# DA_10_-10.net
KiCad netlist of a schematic drawn in Altium Designer
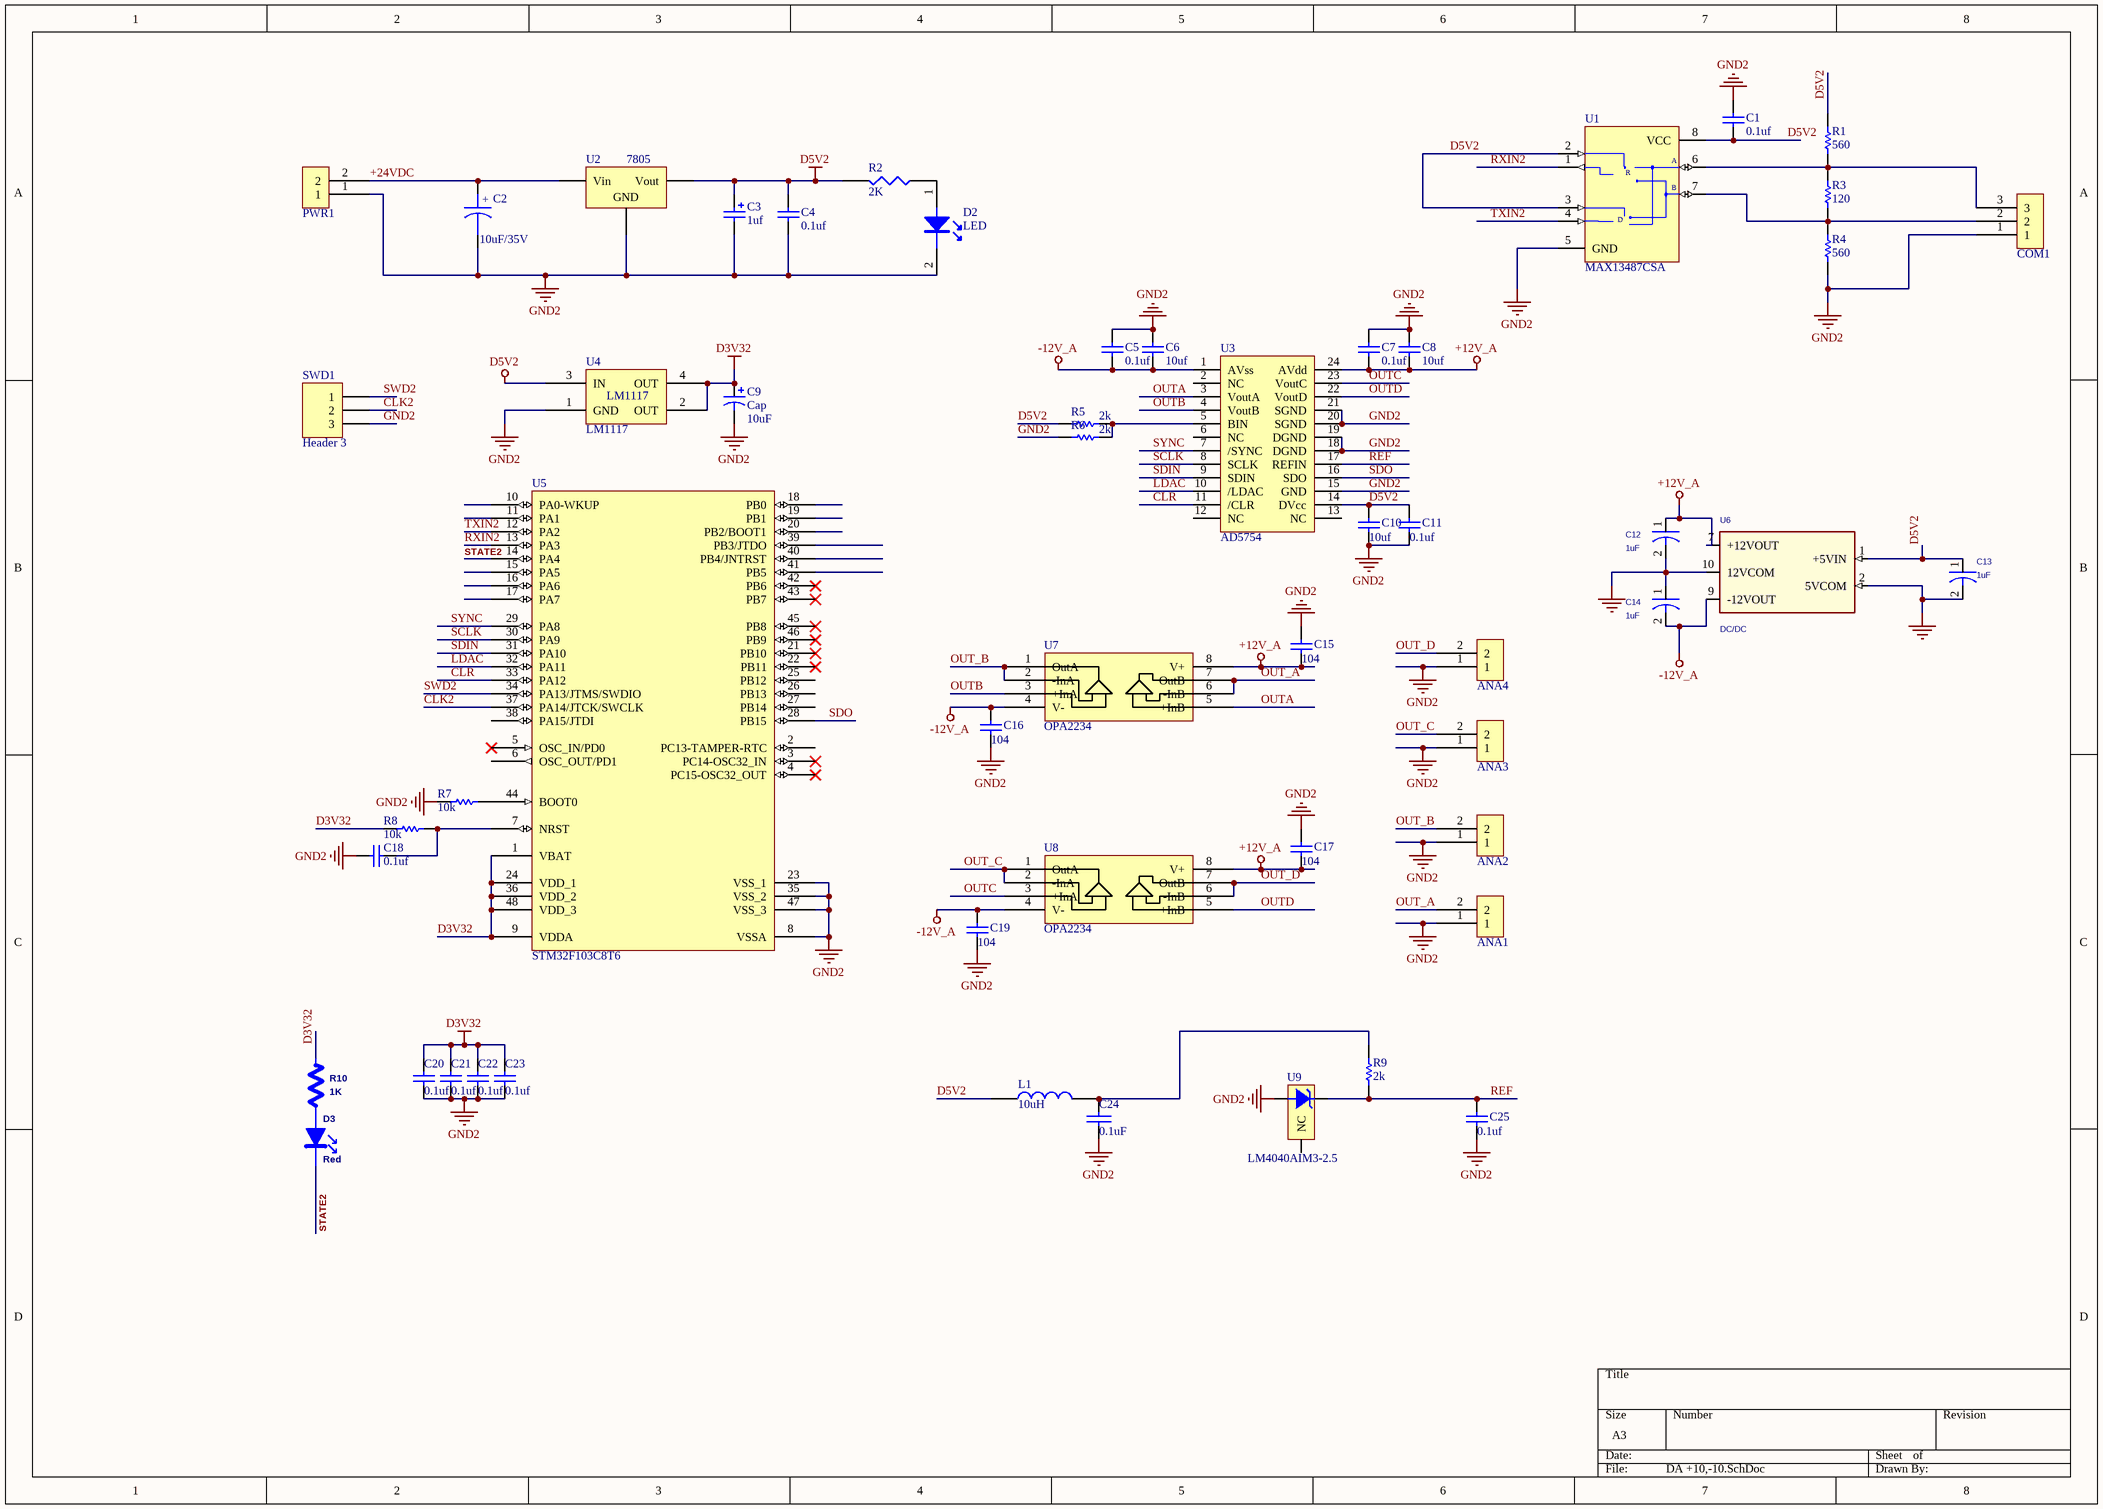
[diagram p0: DA +10,-10.SchDoc]

(export (version "E")
  (design (tool "Eeschema 10.0.6"))
  (components
    (comp (ref "ANA1")
      (value "HDR1*2_3.81")
      (footprint "2P HEADER 3.81 90")
      (libsource (lib "我的器件库") (part "HDR1*2_3.81"))
    )
    (comp (ref "ANA2")
      (value "HDR1*2_3.81")
      (footprint "2P HEADER 3.81 90")
      (libsource (lib "我的器件库") (part "HDR1*2_3.81"))
    )
    (comp (ref "ANA3")
      (value "HDR1*2_3.81")
      (footprint "2P HEADER 3.81 90")
      (libsource (lib "我的器件库") (part "HDR1*2_3.81"))
    )
    (comp (ref "ANA4")
      (value "HDR1*2_3.81")
      (footprint "2P HEADER 3.81 90")
      (libsource (lib "我的器件库") (part "HDR1*2_3.81"))
    )
    (comp (ref "C1")
      (value "0.1uf")
      (footprint "EIA-0805")
      (description "Capacitor")
      (fields (field (name "PUBLISHER") "Altium Limited"))
      (libsource (lib "Miscellaneous Devices") (part "Cap"))
    )
    (comp (ref "C2")
      (value "10uF/35V")
      (footprint "BC-CAP 6.6 X5.4")
      (description "Capacitor")
      (libsource (lib "*") (part "CAPACITOR POL"))
    )
    (comp (ref "C3") (value "1uf") (footprint "EIA-0805") (libsource (lib "我的器件库") (part "CAP")))
    (comp (ref "C4") (value "0.1uf") (footprint "EIA-0805") (libsource (lib "我的器件库") (part "CAP Y1")))
    (comp (ref "C5")
      (value "0.1uf")
      (footprint "EIA-0805")
      (description "Capacitor")
      (fields (field (name "Comment") "1uf") (field (name "PUBLISHER") "Altium Limited"))
      (libsource (lib "Miscellaneous Devices") (part "Cap"))
    )
    (comp (ref "C6")
      (value "10uf")
      (footprint "EIA-0805")
      (description "Capacitor")
      (fields (field (name "Comment") "1uf") (field (name "PUBLISHER") "Altium Limited"))
      (libsource (lib "Miscellaneous Devices") (part "Cap"))
    )
    (comp (ref "C7")
      (value "0.1uf")
      (footprint "EIA-0805")
      (description "Capacitor")
      (fields (field (name "Comment") "1uf") (field (name "PUBLISHER") "Altium Limited"))
      (libsource (lib "Miscellaneous Devices") (part "Cap"))
    )
    (comp (ref "C8")
      (value "10uf")
      (footprint "EIA-0805")
      (description "Capacitor")
      (fields (field (name "Comment") "1uf") (field (name "PUBLISHER") "Altium Limited"))
      (libsource (lib "Miscellaneous Devices") (part "Cap"))
    )
    (comp (ref "C9")
      (value "Cap")
      (footprint "EIA-0805")
      (description "Polarized Capacitor (Radial)")
      (fields (field (name "ALTIUM_VALUE") "10uF") (field (name "PUBLISHER") "Altium Limited"))
      (libsource (lib "Miscellaneous Devices") (part "Cap Pol1"))
    )
    (comp (ref "C10")
      (value "10uf")
      (footprint "EIA-0805")
      (description "Capacitor")
      (fields (field (name "Comment") "1uf") (field (name "PUBLISHER") "Altium Limited"))
      (libsource (lib "Miscellaneous Devices") (part "Cap"))
    )
    (comp (ref "C11")
      (value "0.1uf")
      (footprint "EIA-0805")
      (description "Capacitor")
      (fields (field (name "Comment") "1uf") (field (name "PUBLISHER") "Altium Limited"))
      (libsource (lib "Miscellaneous Devices") (part "Cap"))
    )
    (comp (ref "C12")
      (value "1uF")
      (fields
        (field (name "MFGRS PART NUM") "ECJ-3YB1E105K")
        (field (name "PART NUMBER") "CAP-500525")
        (field (name "MANUFACTURER") "Panasonic")
      )
      (libsource (lib "*") (part "CAP"))
    )
    (comp (ref "C13")
      (value "1uF")
      (fields
        (field (name "MFGRS PART NUM") "ECJ-3YB1E105K")
        (field (name "PART NUMBER") "CAP-500525")
        (field (name "MANUFACTURER") "Panasonic")
      )
      (libsource (lib "*") (part "CAP"))
    )
    (comp (ref "C14")
      (value "1uF")
      (fields
        (field (name "MFGRS PART NUM") "ECJ-3YB1E105K")
        (field (name "PART NUMBER") "CAP-500525")
        (field (name "MANUFACTURER") "Panasonic")
      )
      (libsource (lib "*") (part "CAP"))
    )
    (comp (ref "C15")
      (value "104")
      (footprint "EIA-0805")
      (description "Capacitor")
      (fields (field (name "Comment") "1uf") (field (name "PUBLISHER") "Altium Limited"))
      (libsource (lib "Miscellaneous Devices") (part "Cap"))
    )
    (comp (ref "C16")
      (value "104")
      (footprint "EIA-0805")
      (description "Capacitor")
      (fields (field (name "Comment") "1uf") (field (name "PUBLISHER") "Altium Limited"))
      (libsource (lib "Miscellaneous Devices") (part "Cap"))
    )
    (comp (ref "C17")
      (value "104")
      (footprint "EIA-0805")
      (description "Capacitor")
      (fields (field (name "Comment") "1uf") (field (name "PUBLISHER") "Altium Limited"))
      (libsource (lib "Miscellaneous Devices") (part "Cap"))
    )
    (comp (ref "C18")
      (value "0.1uf")
      (footprint "EIA-0805")
      (description "Capacitor")
      (fields (field (name "PUBLISHER") "Altium Limited"))
      (libsource (lib "Miscellaneous Devices") (part "Cap"))
    )
    (comp (ref "C19")
      (value "104")
      (footprint "EIA-0805")
      (description "Capacitor")
      (fields (field (name "Comment") "1uf") (field (name "PUBLISHER") "Altium Limited"))
      (libsource (lib "Miscellaneous Devices") (part "Cap"))
    )
    (comp (ref "C20")
      (value "0.1uf")
      (footprint "EIA-0805")
      (description "Capacitor")
      (fields (field (name "PUBLISHER") "Altium Limited"))
      (libsource (lib "Miscellaneous Devices") (part "Cap"))
    )
    (comp (ref "C21")
      (value "0.1uf")
      (footprint "EIA-0805")
      (description "Capacitor")
      (fields (field (name "PUBLISHER") "Altium Limited"))
      (libsource (lib "Miscellaneous Devices") (part "Cap"))
    )
    (comp (ref "C22")
      (value "0.1uf")
      (footprint "EIA-0805")
      (description "Capacitor")
      (fields (field (name "PUBLISHER") "Altium Limited"))
      (libsource (lib "Miscellaneous Devices") (part "Cap"))
    )
    (comp (ref "C23")
      (value "0.1uf")
      (footprint "EIA-0805")
      (description "Capacitor")
      (fields (field (name "PUBLISHER") "Altium Limited"))
      (libsource (lib "Miscellaneous Devices") (part "Cap"))
    )
    (comp (ref "C24")
      (value "0.1uF")
      (footprint "EIA-0805")
      (description "Capacitor")
      (libsource (lib "") (part "CAP_1"))
    )
    (comp (ref "C25")
      (value "0.1uf")
      (footprint "EIA-0805")
      (description "Capacitor")
      (fields (field (name "Comment") "1uf") (field (name "PUBLISHER") "Altium Limited"))
      (libsource (lib "Miscellaneous Devices") (part "Cap"))
    )
    (comp (ref "COM1")
      (value "HDR1*3_3.81")
      (footprint "3P HEADER 3.81 90")
      (libsource (lib "我的器件库") (part "HDR1*3_3.81"))
    )
    (comp (ref "D2") (value "LED") (footprint "0805_L") (libsource (lib "backup of send") (part "LED")))
    (comp (ref "D3")
      (value "BC_LED")
      (footprint "0805_L")
      (fields (field (name "COLOR") "Red"))
      (libsource (lib "TYT") (part "BC_LED"))
    )
    (comp (ref "L1") (value "10uH") (footprint "C1206") (libsource (lib "*") (part "INDUCTOR")))
    (comp (ref "PWR1")
      (value "HDR1*2_3.81")
      (footprint "2P HEADER 3.81 90")
      (libsource (lib "") (part "HDR1*2_3.81_1"))
    )
    (comp (ref "R1")
      (value "560")
      (footprint "EIA-0805")
      (description "Resistor")
      (fields (field (name "PUBLISHER") "Altium Limited"))
      (libsource (lib "Miscellaneous Devices") (part "Res1"))
    )
    (comp (ref "R2") (value "2K") (footprint "EIA-0805") (libsource (lib "*") (part "RES1")))
    (comp (ref "R3")
      (value "120")
      (footprint "EIA-0805")
      (description "Resistor")
      (fields (field (name "PUBLISHER") "Altium Limited"))
      (libsource (lib "Miscellaneous Devices") (part "Res1"))
    )
    (comp (ref "R4")
      (value "560")
      (footprint "EIA-0805")
      (description "Resistor")
      (fields (field (name "PUBLISHER") "Altium Limited"))
      (libsource (lib "Miscellaneous Devices") (part "Res1"))
    )
    (comp (ref "R5")
      (value "2k")
      (footprint "EIA-0805")
      (description "Resistor")
      (fields (field (name "PUBLISHER") "Altium Limited"))
      (libsource (lib "Miscellaneous Devices") (part "Res1"))
    )
    (comp (ref "R6")
      (value "2k")
      (footprint "EIA-0805")
      (description "Resistor")
      (fields (field (name "PUBLISHER") "Altium Limited"))
      (libsource (lib "Miscellaneous Devices") (part "Res1"))
    )
    (comp (ref "R7")
      (value "10k")
      (footprint "EIA-0805")
      (description "Resistor")
      (fields (field (name "PUBLISHER") "Altium Limited"))
      (libsource (lib "Miscellaneous Devices") (part "Res1"))
    )
    (comp (ref "R8")
      (value "10k")
      (footprint "EIA-0805")
      (description "Resistor")
      (fields (field (name "PUBLISHER") "Altium Limited"))
      (libsource (lib "Miscellaneous Devices") (part "Res1"))
    )
    (comp (ref "R9")
      (value "2k")
      (footprint "EIA-0805")
      (description "Resistor")
      (fields (field (name "PUBLISHER") "Altium Limited"))
      (libsource (lib "Miscellaneous Devices") (part "Res1"))
    )
    (comp (ref "R10") (value "1K") (footprint "EIA-0805") (libsource (lib "TYT") (part "BC_R")))
    (comp (ref "SWD1")
      (value "Header 3")
      (footprint "HDR1X3")
      (description "Header, 3-Pin")
      (fields (field (name "PUBLISHER") "Altium Limited"))
      (libsource (lib "Miscellaneous Connectors") (part "Header 3"))
    )
    (comp (ref "U1")
      (value "MAX13487CSA")
      (footprint "SO8_L")
      (description "Low-Power, Slew-Rate-Limited RS-485/RS-422 Transceiver")
      (fields (field (name "PUBLISHER") "Altium Limited"))
      (libsource (lib "Maxim Communication Transceiver") (part "MAX485CSA"))
    )
    (comp (ref "U2")
      (value "7805")
      (footprint "TO220")
      (description "Voltage Regulator")
      (fields (field (name "PUBLISHER") "Altium Limited"))
      (libsource (lib "Miscellaneous Devices") (part "Volt Reg"))
    )
    (comp (ref "U3") (value "AD5754") (footprint "TSSOP_24") (libsource (lib "我的器件库") (part "AD5754")))
    (comp (ref "U4") (value "LM1117") (footprint "SOT223_L") (libsource (lib "TYT") (part "LM1117")))
    (comp (ref "U5")
      (value "STM32F103C8T6")
      (footprint "PQFP-48-7*7")
      (description "STM32 ARM-based 32-bit MCU with 64 Kbytes Flash, 48-pin LQFP, Industrial Temperature")
      (fields (field (name "PUBLISHER") "Altium Limited"))
      (libsource (lib "ST Microcontroller 32-Bit STM32") (part "STM32F103C8T6"))
    )
    (comp (ref "U6")
      (value "DC/DC")
      (fields
        (field (name "MANUFACTURER") "Power One")
        (field (name "PART NUMBER") "ASY-503927")
        (field (name "MFGRS PART NUM") "DSP1N5D12")
      )
      (libsource (lib "*") (part "DC/DC-051212_0"))
    )
    (comp (ref "U7") (value "OPA2234") (footprint "SO8_L") (libsource (lib "我的封装") (part "OPA2234")))
    (comp (ref "U8") (value "OPA2234") (footprint "SO8_L") (libsource (lib "我的封装") (part "OPA2234")))
    (comp (ref "U9")
      (value "LM4040AIM3-2.5")
      (footprint "SOT23_L")
      (description "Precision Micropower Shunt Voltage Reference")
      (fields
        (field (name "MANUFACTURER") "National Semiconductor")
        (field (name "DIGIKEYPARTNUMBER") "LM4040AIM3-2.5CT-ND")
        (field (name "PUBLISHER") "Altium Limited")
      )
      (libsource (lib "NSC Voltage Reference") (part "LM4040AIM3-2.5"))
    )
  )
  (nets
    (net (code "1") (name "+12V_A") (class "Default")
      (node (ref "C12") (pin "1") (pinfunction "1_1") (pintype "passive"))
      (node (ref "C15") (pin "2") (pinfunction "2_2") (pintype "passive"))
      (node (ref "C17") (pin "2") (pinfunction "2_2") (pintype "passive"))
      (node (ref "C7") (pin "1") (pinfunction "1_1") (pintype "passive"))
      (node (ref "C8") (pin "1") (pinfunction "1_1") (pintype "passive"))
      (node (ref "U3") (pin "24") (pinfunction "AVdd_24") (pintype "passive"))
      (node (ref "U6") (pin "7") (pinfunction "+12VOUT_7") (pintype "passive"))
      (node (ref "U7") (pin "8") (pinfunction "V+_8") (pintype "passive"))
      (node (ref "U8") (pin "8") (pinfunction "V+_8") (pintype "passive"))
    )
    (net (code "2") (name "-12V_A") (class "Default")
      (node (ref "C14") (pin "2") (pinfunction "2_2") (pintype "passive"))
      (node (ref "C16") (pin "1") (pinfunction "1_1") (pintype "passive"))
      (node (ref "C19") (pin "1") (pinfunction "1_1") (pintype "passive"))
      (node (ref "C5") (pin "1") (pinfunction "1_1") (pintype "passive"))
      (node (ref "C6") (pin "1") (pinfunction "1_1") (pintype "passive"))
      (node (ref "U3") (pin "1") (pinfunction "AVss_1") (pintype "passive"))
      (node (ref "U6") (pin "9") (pinfunction "-12VOUT_9") (pintype "passive"))
      (node (ref "U7") (pin "4") (pinfunction "V-_4") (pintype "passive"))
      (node (ref "U8") (pin "4") (pinfunction "V-_4") (pintype "passive"))
    )
    (net (code "3") (name "/+24VDC") (class "Default")
      (node (ref "C2") (pin "1") (pinfunction "1_1") (pintype "passive"))
      (node (ref "PWR1") (pin "2") (pinfunction "2_2") (pintype "passive"))
      (node (ref "U2") (pin "1") (pinfunction "Vin_1") (pintype "passive"))
    )
    (net (code "4") (name "/CLK2") (class "Default")
      (node (ref "SWD1") (pin "2") (pinfunction "2_2") (pintype "passive"))
      (node (ref "U5") (pin "37") (pinfunction "PA14/JTCK/SWCLK_37") (pintype "bidirectional"))
    )
    (net (code "5") (name "/CLR") (class "Default")
      (node (ref "U3") (pin "11") (pinfunction "/CLR_11") (pintype "passive"))
      (node (ref "U5") (pin "33") (pinfunction "PA12_33") (pintype "bidirectional"))
    )
    (net (code "6") (name "/LDAC") (class "Default")
      (node (ref "U3") (pin "10") (pinfunction "/LDAC_10") (pintype "passive"))
      (node (ref "U5") (pin "32") (pinfunction "PA11_32") (pintype "bidirectional"))
    )
    (net (code "7") (name "/OUTA") (class "Default")
      (node (ref "U3") (pin "3") (pinfunction "VoutA_3") (pintype "passive"))
      (node (ref "U7") (pin "5") (pinfunction "+InB_5") (pintype "passive"))
    )
    (net (code "8") (name "/OUTB") (class "Default")
      (node (ref "U3") (pin "4") (pinfunction "VoutB_4") (pintype "passive"))
      (node (ref "U7") (pin "3") (pinfunction "+InA_3") (pintype "passive"))
    )
    (net (code "9") (name "/OUTC") (class "Default")
      (node (ref "U3") (pin "23") (pinfunction "VoutC_23") (pintype "passive"))
      (node (ref "U8") (pin "3") (pinfunction "+InA_3") (pintype "passive"))
    )
    (net (code "10") (name "/OUTD") (class "Default")
      (node (ref "U3") (pin "22") (pinfunction "VoutD_22") (pintype "passive"))
      (node (ref "U8") (pin "5") (pinfunction "+InB_5") (pintype "passive"))
    )
    (net (code "11") (name "/OUT_A") (class "Default")
      (node (ref "ANA1") (pin "2") (pinfunction "2_2") (pintype "passive"))
      (node (ref "U7") (pin "6") (pinfunction "-InB_6") (pintype "passive"))
      (node (ref "U7") (pin "7") (pinfunction "OutB_7") (pintype "passive"))
    )
    (net (code "12") (name "/OUT_B") (class "Default")
      (node (ref "ANA2") (pin "2") (pinfunction "2_2") (pintype "passive"))
      (node (ref "U7") (pin "1") (pinfunction "OutA_1") (pintype "passive"))
      (node (ref "U7") (pin "2") (pinfunction "-InA_2") (pintype "passive"))
    )
    (net (code "13") (name "/OUT_C") (class "Default")
      (node (ref "ANA3") (pin "2") (pinfunction "2_2") (pintype "passive"))
      (node (ref "U8") (pin "1") (pinfunction "OutA_1") (pintype "passive"))
      (node (ref "U8") (pin "2") (pinfunction "-InA_2") (pintype "passive"))
    )
    (net (code "14") (name "/OUT_D") (class "Default")
      (node (ref "ANA4") (pin "2") (pinfunction "2_2") (pintype "passive"))
      (node (ref "U8") (pin "6") (pinfunction "-InB_6") (pintype "passive"))
      (node (ref "U8") (pin "7") (pinfunction "OutB_7") (pintype "passive"))
    )
    (net (code "15") (name "/REF") (class "Default")
      (node (ref "C25") (pin "1") (pinfunction "1_1") (pintype "passive"))
      (node (ref "R9") (pin "2") (pinfunction "2_2") (pintype "passive"))
      (node (ref "U3") (pin "17") (pinfunction "REFIN_17") (pintype "passive"))
      (node (ref "U9") (pin "1") (pinfunction "+V_1") (pintype "passive"))
    )
    (net (code "16") (name "/RXIN2") (class "Default")
      (node (ref "U1") (pin "1") (pinfunction "RO_1") (pintype "output"))
      (node (ref "U5") (pin "13") (pinfunction "PA3_13") (pintype "bidirectional"))
    )
    (net (code "17") (name "/SCLK") (class "Default")
      (node (ref "U3") (pin "8") (pinfunction "SCLK_8") (pintype "passive"))
      (node (ref "U5") (pin "30") (pinfunction "PA9_30") (pintype "bidirectional"))
    )
    (net (code "18") (name "/SDIN") (class "Default")
      (node (ref "U3") (pin "9") (pinfunction "SDIN_9") (pintype "passive"))
      (node (ref "U5") (pin "31") (pinfunction "PA10_31") (pintype "bidirectional"))
    )
    (net (code "19") (name "/SDO") (class "Default")
      (node (ref "U3") (pin "16") (pinfunction "SDO_16") (pintype "passive"))
      (node (ref "U5") (pin "28") (pinfunction "PB15_28") (pintype "bidirectional"))
    )
    (net (code "20") (name "/STATE2") (class "Default")
      (node (ref "D3") (pin "2") (pinfunction "2_2") (pintype "passive"))
      (node (ref "U5") (pin "14") (pinfunction "PA4_14") (pintype "bidirectional"))
    )
    (net (code "21") (name "/SWD2") (class "Default")
      (node (ref "SWD1") (pin "1") (pinfunction "1_1") (pintype "passive"))
      (node (ref "U5") (pin "34") (pinfunction "PA13/JTMS/SWDIO_34") (pintype "bidirectional"))
    )
    (net (code "22") (name "/SYNC") (class "Default")
      (node (ref "U3") (pin "7") (pinfunction "/SYNC_7") (pintype "passive"))
      (node (ref "U5") (pin "29") (pinfunction "PA8_29") (pintype "bidirectional"))
    )
    (net (code "23") (name "/TXIN2") (class "Default")
      (node (ref "U1") (pin "4") (pinfunction "DI_4") (pintype "input"))
      (node (ref "U5") (pin "12") (pinfunction "PA2_12") (pintype "bidirectional"))
    )
    (net (code "24") (name "D3V32") (class "Default")
      (node (ref "C20") (pin "1") (pinfunction "1_1") (pintype "passive"))
      (node (ref "C21") (pin "1") (pinfunction "1_1") (pintype "passive"))
      (node (ref "C22") (pin "1") (pinfunction "1_1") (pintype "passive"))
      (node (ref "C23") (pin "1") (pinfunction "1_1") (pintype "passive"))
      (node (ref "C9") (pin "1") (pinfunction "1_1") (pintype "passive"))
      (node (ref "R10") (pin "2") (pinfunction "2_2") (pintype "passive"))
      (node (ref "R8") (pin "1") (pinfunction "1_1") (pintype "passive"))
      (node (ref "U4") (pin "2") (pinfunction "OUT_2") (pintype "passive"))
      (node (ref "U4") (pin "4") (pinfunction "OUT_4") (pintype "passive"))
      (node (ref "U5") (pin "1") (pinfunction "VBAT_1") (pintype "power_in"))
      (node (ref "U5") (pin "24") (pinfunction "VDD_1_24") (pintype "power_in"))
      (node (ref "U5") (pin "36") (pinfunction "VDD_2_36") (pintype "power_in"))
      (node (ref "U5") (pin "48") (pinfunction "VDD_3_48") (pintype "power_in"))
      (node (ref "U5") (pin "9") (pinfunction "VDDA_9") (pintype "power_in"))
    )
    (net (code "25") (name "D5V2") (class "Default")
      (node (ref "C1") (pin "1") (pinfunction "1_1") (pintype "passive"))
      (node (ref "C10") (pin "1") (pinfunction "1_1") (pintype "passive"))
      (node (ref "C11") (pin "1") (pinfunction "1_1") (pintype "passive"))
      (node (ref "C13") (pin "1") (pinfunction "1_1") (pintype "passive"))
      (node (ref "C3") (pin "1") (pinfunction "1_1") (pintype "passive"))
      (node (ref "C4") (pin "2") (pinfunction "2_2") (pintype "passive"))
      (node (ref "L1") (pin "1") (pinfunction "1_1") (pintype "passive"))
      (node (ref "R1") (pin "1") (pinfunction "1_1") (pintype "passive"))
      (node (ref "R2") (pin "2") (pinfunction "2_2") (pintype "passive"))
      (node (ref "R5") (pin "1") (pinfunction "1_1") (pintype "passive"))
      (node (ref "U1") (pin "2") (pinfunction "~{RE}_2") (pintype "input"))
      (node (ref "U1") (pin "3") (pinfunction "DE_3") (pintype "input"))
      (node (ref "U1") (pin "8") (pinfunction "VCC_8") (pintype "power_in"))
      (node (ref "U2") (pin "3") (pinfunction "Vout_3") (pintype "passive"))
      (node (ref "U3") (pin "14") (pinfunction "DVcc_14") (pintype "passive"))
      (node (ref "U4") (pin "3") (pinfunction "IN_3") (pintype "passive"))
      (node (ref "U6") (pin "1") (pinfunction "+5VIN_1") (pintype "input"))
    )
    (net (code "26") (name "GND2") (class "Default")
      (node (ref "ANA1") (pin "1") (pinfunction "1_1") (pintype "passive"))
      (node (ref "ANA2") (pin "1") (pinfunction "1_1") (pintype "passive"))
      (node (ref "ANA3") (pin "1") (pinfunction "1_1") (pintype "passive"))
      (node (ref "ANA4") (pin "1") (pinfunction "1_1") (pintype "passive"))
      (node (ref "C1") (pin "2") (pinfunction "2_2") (pintype "passive"))
      (node (ref "C10") (pin "2") (pinfunction "2_2") (pintype "passive"))
      (node (ref "C11") (pin "2") (pinfunction "2_2") (pintype "passive"))
      (node (ref "C12") (pin "2") (pinfunction "2_2") (pintype "passive"))
      (node (ref "C13") (pin "2") (pinfunction "2_2") (pintype "passive"))
      (node (ref "C14") (pin "1") (pinfunction "1_1") (pintype "passive"))
      (node (ref "C15") (pin "1") (pinfunction "1_1") (pintype "passive"))
      (node (ref "C16") (pin "2") (pinfunction "2_2") (pintype "passive"))
      (node (ref "C17") (pin "1") (pinfunction "1_1") (pintype "passive"))
      (node (ref "C18") (pin "2") (pinfunction "2_2") (pintype "passive"))
      (node (ref "C19") (pin "2") (pinfunction "2_2") (pintype "passive"))
      (node (ref "C2") (pin "2") (pinfunction "2_2") (pintype "passive"))
      (node (ref "C20") (pin "2") (pinfunction "2_2") (pintype "passive"))
      (node (ref "C21") (pin "2") (pinfunction "2_2") (pintype "passive"))
      (node (ref "C22") (pin "2") (pinfunction "2_2") (pintype "passive"))
      (node (ref "C23") (pin "2") (pinfunction "2_2") (pintype "passive"))
      (node (ref "C24") (pin "2") (pinfunction "2_2") (pintype "passive"))
      (node (ref "C25") (pin "2") (pinfunction "2_2") (pintype "passive"))
      (node (ref "C3") (pin "2") (pinfunction "2_2") (pintype "passive"))
      (node (ref "C4") (pin "1") (pinfunction "1_1") (pintype "passive"))
      (node (ref "C5") (pin "2") (pinfunction "2_2") (pintype "passive"))
      (node (ref "C6") (pin "2") (pinfunction "2_2") (pintype "passive"))
      (node (ref "C7") (pin "2") (pinfunction "2_2") (pintype "passive"))
      (node (ref "C8") (pin "2") (pinfunction "2_2") (pintype "passive"))
      (node (ref "C9") (pin "2") (pinfunction "2_2") (pintype "passive"))
      (node (ref "COM1") (pin "1") (pinfunction "1_1") (pintype "passive"))
      (node (ref "D2") (pin "2") (pinfunction "2_2") (pintype "passive"))
      (node (ref "PWR1") (pin "1") (pinfunction "1_1") (pintype "passive"))
      (node (ref "R4") (pin "2") (pinfunction "2_2") (pintype "passive"))
      (node (ref "R6") (pin "1") (pinfunction "1_1") (pintype "passive"))
      (node (ref "R7") (pin "1") (pinfunction "1_1") (pintype "passive"))
      (node (ref "SWD1") (pin "3") (pinfunction "3_3") (pintype "passive"))
      (node (ref "U1") (pin "5") (pinfunction "GND_5") (pintype "power_in"))
      (node (ref "U2") (pin "2") (pinfunction "GND_2") (pintype "passive"))
      (node (ref "U3") (pin "15") (pinfunction "GND_15") (pintype "passive"))
      (node (ref "U3") (pin "18") (pinfunction "DGND_18") (pintype "passive"))
      (node (ref "U3") (pin "19") (pinfunction "DGND_19") (pintype "passive"))
      (node (ref "U3") (pin "20") (pinfunction "SGND_20") (pintype "passive"))
      (node (ref "U3") (pin "21") (pinfunction "SGND_21") (pintype "passive"))
      (node (ref "U4") (pin "1") (pinfunction "GND_1") (pintype "passive"))
      (node (ref "U5") (pin "23") (pinfunction "VSS_1_23") (pintype "power_in"))
      (node (ref "U5") (pin "35") (pinfunction "VSS_2_35") (pintype "power_in"))
      (node (ref "U5") (pin "47") (pinfunction "VSS_3_47") (pintype "power_in"))
      (node (ref "U5") (pin "8") (pinfunction "VSSA_8") (pintype "power_in"))
      (node (ref "U6") (pin "10") (pinfunction "12VCOM_10") (pintype "passive"))
      (node (ref "U6") (pin "2") (pinfunction "5VCOM_2") (pintype "input"))
      (node (ref "U9") (pin "2") (pinfunction "-V_2") (pintype "passive"))
    )
    (net (code "27") (name "Net-(C24-Pad1)") (class "Default")
      (node (ref "C24") (pin "1") (pinfunction "1_1") (pintype "passive"))
      (node (ref "L1") (pin "2") (pinfunction "2_2") (pintype "passive"))
      (node (ref "R9") (pin "1") (pinfunction "1_1") (pintype "passive"))
    )
    (net (code "28") (name "Net-(D2-Pad1)") (class "Default")
      (node (ref "D2") (pin "1") (pinfunction "1_1") (pintype "passive"))
      (node (ref "R2") (pin "1") (pinfunction "1_1") (pintype "passive"))
    )
    (net (code "29") (name "Net-(D3-Pad1)") (class "Default")
      (node (ref "D3") (pin "1") (pinfunction "1_1") (pintype "passive"))
      (node (ref "R10") (pin "1") (pinfunction "1_1") (pintype "passive"))
    )
    (net (code "30") (name "Net-(U1-A)") (class "Default")
      (node (ref "COM1") (pin "3") (pinfunction "3_3") (pintype "passive"))
      (node (ref "R1") (pin "2") (pinfunction "2_2") (pintype "passive"))
      (node (ref "R3") (pin "1") (pinfunction "1_1") (pintype "passive"))
      (node (ref "U1") (pin "6") (pinfunction "A_6") (pintype "bidirectional"))
    )
    (net (code "31") (name "Net-(U1-B)") (class "Default")
      (node (ref "COM1") (pin "2") (pinfunction "2_2") (pintype "passive"))
      (node (ref "R3") (pin "2") (pinfunction "2_2") (pintype "passive"))
      (node (ref "R4") (pin "1") (pinfunction "1_1") (pintype "passive"))
      (node (ref "U1") (pin "7") (pinfunction "B_7") (pintype "bidirectional"))
    )
    (net (code "32") (name "Net-(U3-BIN)") (class "Default")
      (node (ref "R5") (pin "2") (pinfunction "2_2") (pintype "passive"))
      (node (ref "R6") (pin "2") (pinfunction "2_2") (pintype "passive"))
      (node (ref "U3") (pin "5") (pinfunction "BIN_5") (pintype "passive"))
    )
    (net (code "33") (name "Net-(U5-BOOT0)") (class "Default")
      (node (ref "R7") (pin "2") (pinfunction "2_2") (pintype "passive"))
      (node (ref "U5") (pin "44") (pinfunction "BOOT0_44") (pintype "input"))
    )
    (net (code "34") (name "Net-(U5-NRST)") (class "Default")
      (node (ref "C18") (pin "1") (pinfunction "1_1") (pintype "passive"))
      (node (ref "R8") (pin "2") (pinfunction "2_2") (pintype "passive"))
      (node (ref "U5") (pin "7") (pinfunction "NRST_7") (pintype "bidirectional"))
    )
    (net (code "35") (name "unconnected-(U3-NC-Pad2)") (class "Default")
      (node (ref "U3") (pin "2") (pinfunction "NC_2") (pintype "passive"))
    )
    (net (code "36") (name "unconnected-(U3-NC-Pad6)") (class "Default")
      (node (ref "U3") (pin "6") (pinfunction "NC_6") (pintype "passive"))
    )
    (net (code "37") (name "unconnected-(U3-NC-Pad12)") (class "Default")
      (node (ref "U3") (pin "12") (pinfunction "NC_12") (pintype "passive"))
    )
    (net (code "38") (name "unconnected-(U3-NC-Pad13)") (class "Default")
      (node (ref "U3") (pin "13") (pinfunction "NC_13") (pintype "passive"))
    )
    (net (code "39") (name "unconnected-(U5-OSC_IN{slash}PD0-Pad5)") (class "Default")
      (node (ref "U5") (pin "5") (pinfunction "OSC_IN/PD0_5") (pintype "input+no_connect"))
    )
    (net (code "40") (name "unconnected-(U5-OSC_OUT{slash}PD1-Pad6)") (class "Default")
      (node (ref "U5") (pin "6") (pinfunction "OSC_OUT/PD1_6") (pintype "output"))
    )
    (net (code "41") (name "unconnected-(U5-PA0-WKUP-Pad10)") (class "Default")
      (node (ref "U5") (pin "10") (pinfunction "PA0-WKUP_10") (pintype "bidirectional"))
    )
    (net (code "42") (name "unconnected-(U5-PA1-Pad11)") (class "Default")
      (node (ref "U5") (pin "11") (pinfunction "PA1_11") (pintype "bidirectional"))
    )
    (net (code "43") (name "unconnected-(U5-PA5-Pad15)") (class "Default")
      (node (ref "U5") (pin "15") (pinfunction "PA5_15") (pintype "bidirectional"))
    )
    (net (code "44") (name "unconnected-(U5-PA6-Pad16)") (class "Default")
      (node (ref "U5") (pin "16") (pinfunction "PA6_16") (pintype "bidirectional"))
    )
    (net (code "45") (name "unconnected-(U5-PA7-Pad17)") (class "Default")
      (node (ref "U5") (pin "17") (pinfunction "PA7_17") (pintype "bidirectional"))
    )
    (net (code "46") (name "unconnected-(U5-PA15{slash}JTDI-Pad38)") (class "Default")
      (node (ref "U5") (pin "38") (pinfunction "PA15/JTDI_38") (pintype "bidirectional"))
    )
    (net (code "47") (name "unconnected-(U5-PB0-Pad18)") (class "Default")
      (node (ref "U5") (pin "18") (pinfunction "PB0_18") (pintype "bidirectional"))
    )
    (net (code "48") (name "unconnected-(U5-PB1-Pad19)") (class "Default")
      (node (ref "U5") (pin "19") (pinfunction "PB1_19") (pintype "bidirectional"))
    )
    (net (code "49") (name "unconnected-(U5-PB2{slash}BOOT1-Pad20)") (class "Default")
      (node (ref "U5") (pin "20") (pinfunction "PB2/BOOT1_20") (pintype "bidirectional"))
    )
    (net (code "50") (name "unconnected-(U5-PB3{slash}JTDO-Pad39)") (class "Default")
      (node (ref "U5") (pin "39") (pinfunction "PB3/JTDO_39") (pintype "bidirectional"))
    )
    (net (code "51") (name "unconnected-(U5-PB4{slash}JNTRST-Pad40)") (class "Default")
      (node (ref "U5") (pin "40") (pinfunction "PB4/JNTRST_40") (pintype "bidirectional"))
    )
    (net (code "52") (name "unconnected-(U5-PB5-Pad41)") (class "Default")
      (node (ref "U5") (pin "41") (pinfunction "PB5_41") (pintype "bidirectional"))
    )
    (net (code "53") (name "unconnected-(U5-PB6-Pad42)") (class "Default")
      (node (ref "U5") (pin "42") (pinfunction "PB6_42") (pintype "bidirectional+no_connect"))
    )
    (net (code "54") (name "unconnected-(U5-PB7-Pad43)") (class "Default")
      (node (ref "U5") (pin "43") (pinfunction "PB7_43") (pintype "bidirectional+no_connect"))
    )
    (net (code "55") (name "unconnected-(U5-PB8-Pad45)") (class "Default")
      (node (ref "U5") (pin "45") (pinfunction "PB8_45") (pintype "bidirectional+no_connect"))
    )
    (net (code "56") (name "unconnected-(U5-PB9-Pad46)") (class "Default")
      (node (ref "U5") (pin "46") (pinfunction "PB9_46") (pintype "bidirectional+no_connect"))
    )
    (net (code "57") (name "unconnected-(U5-PB10-Pad21)") (class "Default")
      (node (ref "U5") (pin "21") (pinfunction "PB10_21") (pintype "bidirectional+no_connect"))
    )
    (net (code "58") (name "unconnected-(U5-PB11-Pad22)") (class "Default")
      (node (ref "U5") (pin "22") (pinfunction "PB11_22") (pintype "bidirectional+no_connect"))
    )
    (net (code "59") (name "unconnected-(U5-PB12-Pad25)") (class "Default")
      (node (ref "U5") (pin "25") (pinfunction "PB12_25") (pintype "bidirectional"))
    )
    (net (code "60") (name "unconnected-(U5-PB13-Pad26)") (class "Default")
      (node (ref "U5") (pin "26") (pinfunction "PB13_26") (pintype "bidirectional"))
    )
    (net (code "61") (name "unconnected-(U5-PB14-Pad27)") (class "Default")
      (node (ref "U5") (pin "27") (pinfunction "PB14_27") (pintype "bidirectional"))
    )
    (net (code "62") (name "unconnected-(U5-PC13-TAMPER-RTC-Pad2)") (class "Default")
      (node (ref "U5") (pin "2") (pinfunction "PC13-TAMPER-RTC_2") (pintype "bidirectional"))
    )
    (net (code "63") (name "unconnected-(U5-PC14-OSC32_IN-Pad3)") (class "Default")
      (node (ref "U5") (pin "3") (pinfunction "PC14-OSC32_IN_3") (pintype "bidirectional+no_connect"))
    )
    (net (code "64") (name "unconnected-(U5-PC15-OSC32_OUT-Pad4)") (class "Default")
      (node (ref "U5") (pin "4") (pinfunction "PC15-OSC32_OUT_4") (pintype "bidirectional+no_connect"))
    )
    (net (code "65") (name "unconnected-(U9-NC-Pad3)") (class "Default")
      (node (ref "U9") (pin "3") (pinfunction "NC_3") (pintype "passive"))
    )
  )
)
